# USB_HUB.net
KiCad netlist of a schematic drawn in Altium Designer
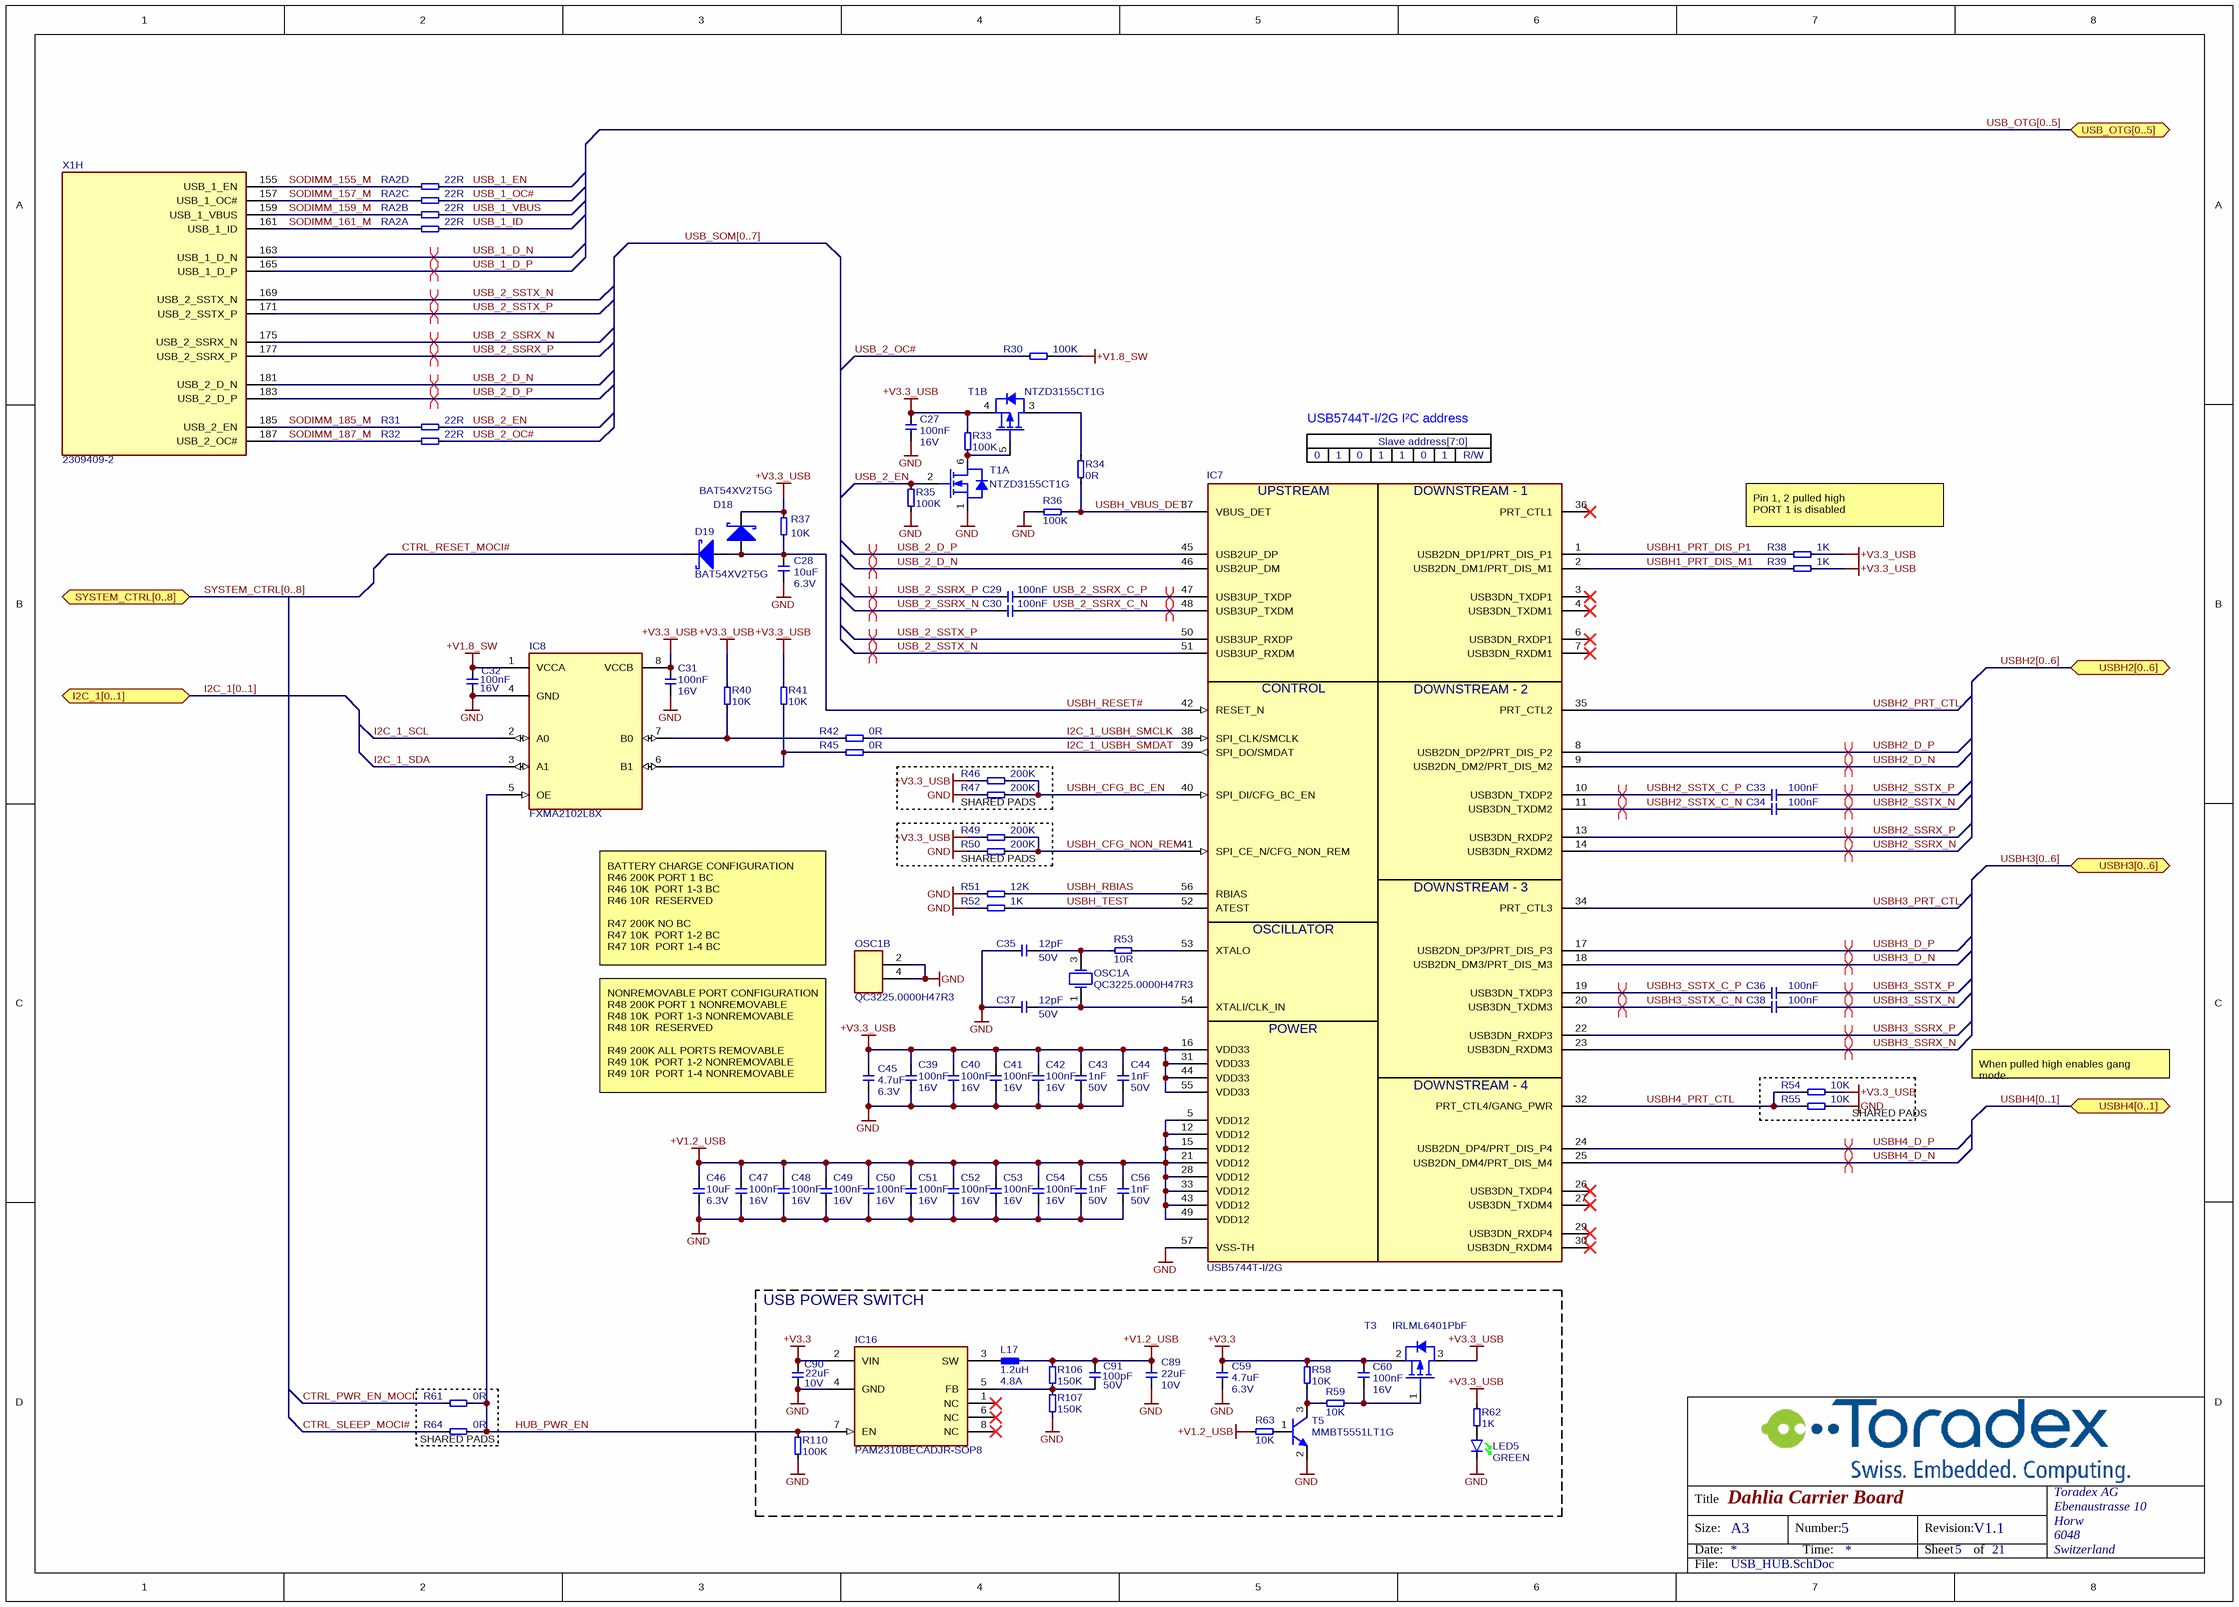
[diagram p0: USB_HUB.SchDoc]

(export (version "E")
  (design (tool "Eeschema 10.0.6"))
  (components
    (comp (ref "C27")
      (value "100nF")
      (footprint "CAPC1005X60N")
      (description "Capacitor Ceramic X7R 100nF 16V 10% 0402")
      (fields (field (name "TOLERANCE") "10%") (field (name "RATING") "16V"))
      (libsource (lib "Dahlia Carrier Board") (part "C-X7R-100nF-16V-10%-0402"))
    )
    (comp (ref "C28")
      (value "10uF")
      (footprint "CAPC1005X60N")
      (description "Capacitor Ceramic X5R 10uF 6.3V 20% 0402")
      (fields (field (name "TOLERANCE") "20%") (field (name "RATING") "6.3V"))
      (libsource (lib "Dahlia Carrier Board") (part "C-X5R-10u-6.3V-20%-0402"))
    )
    (comp (ref "C29")
      (value "100nF")
      (footprint "CAPC1005X60N")
      (description "Capacitor Ceramic X7R 100nF 16V 10% 0402")
      (fields (field (name "TOLERANCE") "10%"))
      (libsource (lib "Dahlia Carrier Board") (part "C-X7R-100nF-16V-10%-0402"))
    )
    (comp (ref "C30")
      (value "100nF")
      (footprint "CAPC1005X60N")
      (description "Capacitor Ceramic X7R 100nF 16V 10% 0402")
      (fields (field (name "TOLERANCE") "10%"))
      (libsource (lib "Dahlia Carrier Board") (part "C-X7R-100nF-16V-10%-0402"))
    )
    (comp (ref "C31")
      (value "100nF")
      (footprint "CAPC1005X60N")
      (description "Capacitor Ceramic X7R 100nF 16V 10% 0402")
      (fields (field (name "TOLERANCE") "10%") (field (name "RATING") "16V"))
      (libsource (lib "Dahlia Carrier Board") (part "C-X7R-100nF-16V-10%-0402"))
    )
    (comp (ref "C32")
      (value "100nF")
      (footprint "CAPC1005X60N")
      (description "Capacitor Ceramic X7R 100nF 16V 10% 0402")
      (fields (field (name "TOLERANCE") "10%") (field (name "RATING") "16V"))
      (libsource (lib "Dahlia Carrier Board") (part "C-X7R-100nF-16V-10%-0402"))
    )
    (comp (ref "C33")
      (value "100nF")
      (footprint "CAPC1005X60N")
      (description "Capacitor Ceramic X7R 100nF 16V 10% 0402")
      (fields (field (name "TOLERANCE") "10%"))
      (libsource (lib "Dahlia Carrier Board") (part "C-X7R-100nF-16V-10%-0402"))
    )
    (comp (ref "C34")
      (value "100nF")
      (footprint "CAPC1005X60N")
      (description "Capacitor Ceramic X7R 100nF 16V 10% 0402")
      (fields (field (name "TOLERANCE") "10%"))
      (libsource (lib "Dahlia Carrier Board") (part "C-X7R-100nF-16V-10%-0402"))
    )
    (comp (ref "C35")
      (value "12pF")
      (footprint "CAPC1005X60N")
      (description "Capacitor Ceramic NP0  12pF 50V 5% 0402")
      (fields (field (name "TOLERANCE") "5%") (field (name "RATING") "50V"))
      (libsource (lib "Dahlia Carrier Board") (part "C-NP0-12p-50V-5%-0402"))
    )
    (comp (ref "C36")
      (value "100nF")
      (footprint "CAPC1005X60N")
      (description "Capacitor Ceramic X7R 100nF 16V 10% 0402")
      (fields (field (name "TOLERANCE") "10%"))
      (libsource (lib "Dahlia Carrier Board") (part "C-X7R-100nF-16V-10%-0402"))
    )
    (comp (ref "C37")
      (value "12pF")
      (footprint "CAPC1005X60N")
      (description "Capacitor Ceramic NP0  12pF 50V 5% 0402")
      (fields (field (name "TOLERANCE") "5%") (field (name "RATING") "50V"))
      (libsource (lib "Dahlia Carrier Board") (part "C-NP0-12p-50V-5%-0402"))
    )
    (comp (ref "C38")
      (value "100nF")
      (footprint "CAPC1005X60N")
      (description "Capacitor Ceramic X7R 100nF 16V 10% 0402")
      (fields (field (name "TOLERANCE") "10%"))
      (libsource (lib "Dahlia Carrier Board") (part "C-X7R-100nF-16V-10%-0402"))
    )
    (comp (ref "C39")
      (value "100nF")
      (footprint "CAPC1005X60N")
      (description "Capacitor Ceramic X7R 100nF 16V 10% 0402")
      (fields (field (name "TOLERANCE") "10%") (field (name "RATING") "16V"))
      (libsource (lib "Dahlia Carrier Board") (part "C-X7R-100nF-16V-10%-0402"))
    )
    (comp (ref "C40")
      (value "100nF")
      (footprint "CAPC1005X60N")
      (description "Capacitor Ceramic X7R 100nF 16V 10% 0402")
      (fields (field (name "TOLERANCE") "10%") (field (name "RATING") "16V"))
      (libsource (lib "Dahlia Carrier Board") (part "C-X7R-100nF-16V-10%-0402"))
    )
    (comp (ref "C41")
      (value "100nF")
      (footprint "CAPC1005X60N")
      (description "Capacitor Ceramic X7R 100nF 16V 10% 0402")
      (fields (field (name "TOLERANCE") "10%") (field (name "RATING") "16V"))
      (libsource (lib "Dahlia Carrier Board") (part "C-X7R-100nF-16V-10%-0402"))
    )
    (comp (ref "C42")
      (value "100nF")
      (footprint "CAPC1005X60N")
      (description "Capacitor Ceramic X7R 100nF 16V 10% 0402")
      (fields (field (name "TOLERANCE") "10%") (field (name "RATING") "16V"))
      (libsource (lib "Dahlia Carrier Board") (part "C-X7R-100nF-16V-10%-0402"))
    )
    (comp (ref "C43")
      (value "1nF")
      (footprint "CAPC1005X60N")
      (description "Capacitor Ceramic X7R 1nF 50V 10% 0402")
      (fields (field (name "TOLERANCE") "10%") (field (name "RATING") "50V"))
      (libsource (lib "Dahlia Carrier Board") (part "C-X7R-1nF-50V-10%-0402"))
    )
    (comp (ref "C44")
      (value "1nF")
      (footprint "CAPC1005X60N")
      (description "Capacitor Ceramic X7R 1nF 50V 10% 0402")
      (fields (field (name "TOLERANCE") "10%") (field (name "RATING") "50V"))
      (libsource (lib "Dahlia Carrier Board") (part "C-X7R-1nF-50V-10%-0402"))
    )
    (comp (ref "C45")
      (value "4.7uF")
      (footprint "CAPC1005X60N")
      (description "Capacitor Ceramic X5R 4.7uF 6.3V 20% 0402")
      (fields (field (name "TOLERANCE") "20%") (field (name "RATING") "6.3V"))
      (libsource (lib "Dahlia Carrier Board") (part "C-X5R-4.7u-6.3V-20%-0402"))
    )
    (comp (ref "C46")
      (value "10uF")
      (footprint "CAPC1005X60N")
      (description "Capacitor Ceramic X5R 10uF 6.3V 20% 0402")
      (fields (field (name "TOLERANCE") "20%") (field (name "RATING") "6.3V"))
      (libsource (lib "Dahlia Carrier Board") (part "C-X5R-10u-6.3V-20%-0402"))
    )
    (comp (ref "C47")
      (value "100nF")
      (footprint "CAPC1005X60N")
      (description "Capacitor Ceramic X7R 100nF 16V 10% 0402")
      (fields (field (name "TOLERANCE") "10%") (field (name "RATING") "16V"))
      (libsource (lib "Dahlia Carrier Board") (part "C-X7R-100nF-16V-10%-0402"))
    )
    (comp (ref "C48")
      (value "100nF")
      (footprint "CAPC1005X60N")
      (description "Capacitor Ceramic X7R 100nF 16V 10% 0402")
      (fields (field (name "TOLERANCE") "10%") (field (name "RATING") "16V"))
      (libsource (lib "Dahlia Carrier Board") (part "C-X7R-100nF-16V-10%-0402"))
    )
    (comp (ref "C49")
      (value "100nF")
      (footprint "CAPC1005X60N")
      (description "Capacitor Ceramic X7R 100nF 16V 10% 0402")
      (fields (field (name "TOLERANCE") "10%") (field (name "RATING") "16V"))
      (libsource (lib "Dahlia Carrier Board") (part "C-X7R-100nF-16V-10%-0402"))
    )
    (comp (ref "C50")
      (value "100nF")
      (footprint "CAPC1005X60N")
      (description "Capacitor Ceramic X7R 100nF 16V 10% 0402")
      (fields (field (name "TOLERANCE") "10%") (field (name "RATING") "16V"))
      (libsource (lib "Dahlia Carrier Board") (part "C-X7R-100nF-16V-10%-0402"))
    )
    (comp (ref "C51")
      (value "100nF")
      (footprint "CAPC1005X60N")
      (description "Capacitor Ceramic X7R 100nF 16V 10% 0402")
      (fields (field (name "TOLERANCE") "10%") (field (name "RATING") "16V"))
      (libsource (lib "Dahlia Carrier Board") (part "C-X7R-100nF-16V-10%-0402"))
    )
    (comp (ref "C52")
      (value "100nF")
      (footprint "CAPC1005X60N")
      (description "Capacitor Ceramic X7R 100nF 16V 10% 0402")
      (fields (field (name "TOLERANCE") "10%") (field (name "RATING") "16V"))
      (libsource (lib "Dahlia Carrier Board") (part "C-X7R-100nF-16V-10%-0402"))
    )
    (comp (ref "C53")
      (value "100nF")
      (footprint "CAPC1005X60N")
      (description "Capacitor Ceramic X7R 100nF 16V 10% 0402")
      (fields (field (name "TOLERANCE") "10%") (field (name "RATING") "16V"))
      (libsource (lib "Dahlia Carrier Board") (part "C-X7R-100nF-16V-10%-0402"))
    )
    (comp (ref "C54")
      (value "100nF")
      (footprint "CAPC1005X60N")
      (description "Capacitor Ceramic X7R 100nF 16V 10% 0402")
      (fields (field (name "TOLERANCE") "10%") (field (name "RATING") "16V"))
      (libsource (lib "Dahlia Carrier Board") (part "C-X7R-100nF-16V-10%-0402"))
    )
    (comp (ref "C55")
      (value "1nF")
      (footprint "CAPC1005X60N")
      (description "Capacitor Ceramic X7R 1nF 50V 10% 0402")
      (fields (field (name "TOLERANCE") "10%") (field (name "RATING") "50V"))
      (libsource (lib "Dahlia Carrier Board") (part "C-X7R-1nF-50V-10%-0402"))
    )
    (comp (ref "C56")
      (value "1nF")
      (footprint "CAPC1005X60N")
      (description "Capacitor Ceramic X7R 1nF 50V 10% 0402")
      (fields (field (name "TOLERANCE") "10%") (field (name "RATING") "50V"))
      (libsource (lib "Dahlia Carrier Board") (part "C-X7R-1nF-50V-10%-0402"))
    )
    (comp (ref "C59")
      (value "4.7uF")
      (footprint "CAPC1005X60N")
      (description "Capacitor Ceramic X5R 4.7uF 6.3V 20% 0402")
      (fields (field (name "TOLERANCE") "20%") (field (name "RATING") "6.3V"))
      (libsource (lib "Dahlia Carrier Board") (part "C-X5R-4.7u-6.3V-20%-0402"))
    )
    (comp (ref "C60")
      (value "100nF")
      (footprint "CAPC1005X60N")
      (description "Capacitor Ceramic X7R 100nF 16V 10% 0402")
      (fields (field (name "TOLERANCE") "10%") (field (name "RATING") "16V"))
      (libsource (lib "Dahlia Carrier Board") (part "C-X7R-100nF-16V-10%-0402"))
    )
    (comp (ref "C89")
      (value "22uF")
      (footprint "T_CAPC0805X125N")
      (description "Capacitor Ceramic X5R 22uF 10V 20% 0805")
      (fields (field (name "TOLERANCE") "20%") (field (name "RATING") "10V"))
      (libsource (lib "Dahlia Carrier Board") (part "C-X5R-22uF-10V-20%-0805"))
    )
    (comp (ref "C90")
      (value "22uF")
      (footprint "T_CAPC0805X125N")
      (description "Capacitor Ceramic X5R 22uF 10V 20% 0805")
      (fields (field (name "TOLERANCE") "20%") (field (name "RATING") "10V"))
      (libsource (lib "Dahlia Carrier Board") (part "C-X5R-22uF-10V-20%-0805"))
    )
    (comp (ref "C91")
      (value "100pF")
      (footprint "CAPC1005X60N")
      (description "Capacitor Ceramic X7R 100pF 50V 10% 0402")
      (fields (field (name "TOLERANCE") "10%") (field (name "RATING") "50V"))
      (libsource (lib "Dahlia Carrier Board") (part "C-X7R-100pF-50V-10%-0402"))
    )
    (comp (ref "D18")
      (value "BAT54XV2T5G")
      (footprint "SOD-523")
      (description "Schottky Barrier Rectifier")
      (fields (field (name "MANUFACTURER PART NO.") "BAT54XV2T5G"))
      (libsource (lib "Dahlia Carrier Board") (part "D-BAT54-SOD523"))
    )
    (comp (ref "D19")
      (value "BAT54XV2T5G")
      (footprint "SOD-523")
      (description "Schottky Barrier Rectifier")
      (fields (field (name "MANUFACTURER PART NO.") "BAT54XV2T5G"))
      (libsource (lib "Dahlia Carrier Board") (part "D-BAT54-SOD523"))
    )
    (comp (ref "IC7")
      (value "USB5744T-I/2G")
      (footprint "IC-QFN40P700X700X100_HS-57N")
      (description "4-Port SS/HS USB 3.0 Controller Hub, VQFN-56, -40C to +85C")
      (libsource (lib "Dahlia Carrier Board") (part "IC-Microchip-USB5744T-I/2G"))
    )
    (comp (ref "IC8")
      (value "FXMA2102L8X")
      (footprint "IC-MicroPak50P160X2160X55-8N")
      (description "Voltage Level Translator for I2C Applications")
      (fields (field (name "MANUFACTURER PART NO.") "FXMA2102L8X"))
      (libsource (lib "Dahlia Carrier Board") (part "IC-ONsemi-FXMA2102L8X"))
    )
    (comp (ref "IC16")
      (value "PAM2310BECADJR")
      (footprint "IC-SO-8EP")
      (description "Integrated Buck Regulator")
      (fields (field (name "MANUFACTURER PART NO.") "PAM2310BECADJR-SOP8"))
      (libsource (lib "Dahlia Carrier Board") (part "IC-DIODES-PAM2310BECADJR-SOP8"))
    )
    (comp (ref "L17")
      (value "1.2uH")
      (footprint "IND-BOURNS-SRP4020TA")
      (description "1.2µH Shielded Wirewound Inductor 4.8A 30mOhm")
      (fields
        (field (name "TOLERANCE") "20%")
        (field (name "MANUFACTURER PART NO.") "SRP4020TA-1R2M")
        (field (name "RATING") "4.8A")
      )
      (libsource (lib "Dahlia Carrier Board") (part "L-Bourns-SRP4020TA-1R2M-1.2uH-4.8A-20%"))
    )
    (comp (ref "LED5")
      (value "LTST-C190GKT")
      (footprint "T_Liteon_LTST-C190GKT")
      (description "LED green Lite-ON LTST-C190GKT")
      (fields (field (name "COLOR") "GREEN"))
      (libsource (lib "Dahlia Carrier Board") (part "LED-LiteOn-LTST-C190GKT"))
    )
    (comp (ref "OSC1")
      (value "QC3225.0000H47R3")
      (footprint "OSC-SMD-3.2mmx2.5mm")
      (description "25MHz Crystal Oscillator, Qantek QC3225.0000H47R3, 20ppm, -40C to +85C, 10pF")
      (fields (field (name "TOLERANCE") "+/- 20 ppm"))
      (libsource (lib "Dahlia Carrier Board") (part "OSC-Qantek-QC3225.0000H47R3"))
    )
    (comp (ref "R30")
      (value "100K")
      (footprint "RESC1005X40N")
      (description "Resistor 100 Kohm 63mW 5% 0402")
      (fields (field (name "TOLERANCE") "5%"))
      (libsource (lib "Dahlia Carrier Board") (part "R-100K-63mW-5%-0402"))
    )
    (comp (ref "R31")
      (value "22R")
      (footprint "RESC1005X40N")
      (description "Resistor 22 ohm 63mW 5% 0402")
      (fields (field (name "TOLERANCE") "5%"))
      (libsource (lib "Dahlia Carrier Board") (part "R-22R-63mW-5%-0402"))
    )
    (comp (ref "R32")
      (value "22R")
      (footprint "RESC1005X40N")
      (description "Resistor 22 ohm 63mW 5% 0402")
      (fields (field (name "TOLERANCE") "5%"))
      (libsource (lib "Dahlia Carrier Board") (part "R-22R-63mW-5%-0402"))
    )
    (comp (ref "R33")
      (value "100K")
      (footprint "RESC1005X40N")
      (description "Resistor 100 Kohm 63mW 5% 0402")
      (fields (field (name "TOLERANCE") "5%"))
      (libsource (lib "Dahlia Carrier Board") (part "R-100K-63mW-5%-0402"))
    )
    (comp (ref "R34")
      (value "0R")
      (footprint "T_RESC0603X30N")
      (description "Resistor 0 ohm 63mW 1% 0603")
      (fields (field (name "TOLERANCE") "1%"))
      (libsource (lib "Dahlia Carrier Board") (part "R-0R-63mW-1%-0603"))
    )
    (comp (ref "R35")
      (value "100K")
      (footprint "RESC1005X40N")
      (description "Resistor 100 Kohm 63mW 5% 0402")
      (fields (field (name "TOLERANCE") "5%"))
      (libsource (lib "Dahlia Carrier Board") (part "R-100K-63mW-5%-0402"))
    )
    (comp (ref "R36")
      (value "100K")
      (footprint "RESC1005X40N")
      (description "Resistor 100 Kohm 63mW 5% 0402")
      (fields (field (name "TOLERANCE") "5%"))
      (libsource (lib "Dahlia Carrier Board") (part "R-100K-63mW-5%-0402"))
    )
    (comp (ref "R37")
      (value "10K")
      (footprint "RESC1005X40N")
      (description "Resistor 10 Kohm 63mW 5% 0402")
      (fields (field (name "TOLERANCE") "5%"))
      (libsource (lib "Dahlia Carrier Board") (part "R-10K-63mW-5%-0402"))
    )
    (comp (ref "R38")
      (value "1K")
      (footprint "RESC1005X40N")
      (description "Resistor 1 Kohm 63mW 5% 0402")
      (fields (field (name "TOLERANCE") "5%"))
      (libsource (lib "Dahlia Carrier Board") (part "R-1K-63mW-5%-0402"))
    )
    (comp (ref "R39")
      (value "1K")
      (footprint "RESC1005X40N")
      (description "Resistor 1 Kohm 63mW 5% 0402")
      (fields (field (name "TOLERANCE") "5%"))
      (libsource (lib "Dahlia Carrier Board") (part "R-1K-63mW-5%-0402"))
    )
    (comp (ref "R40")
      (value "10K")
      (footprint "RESC1005X40N")
      (description "Resistor 10 Kohm 63mW 5% 0402")
      (fields (field (name "TOLERANCE") "5%"))
      (libsource (lib "Dahlia Carrier Board") (part "R-10K-63mW-5%-0402"))
    )
    (comp (ref "R41")
      (value "10K")
      (footprint "RESC1005X40N")
      (description "Resistor 10 Kohm 63mW 5% 0402")
      (fields (field (name "TOLERANCE") "5%"))
      (libsource (lib "Dahlia Carrier Board") (part "R-10K-63mW-5%-0402"))
    )
    (comp (ref "R42")
      (value "0R")
      (footprint "T_RESC0603X30N")
      (description "Resistor 0 ohm 63mW 1% 0603")
      (fields (field (name "TOLERANCE") "1%"))
      (libsource (lib "Dahlia Carrier Board") (part "R-0R-63mW-1%-0603"))
    )
    (comp (ref "R45")
      (value "0R")
      (footprint "T_RESC0603X30N")
      (description "Resistor 0 ohm 63mW 1% 0603")
      (fields (field (name "TOLERANCE") "1%"))
      (libsource (lib "Dahlia Carrier Board") (part "R-0R-63mW-1%-0603"))
    )
    (comp (ref "R46")
      (value "200K")
      (footprint "T_RESC0603X30N")
      (description "Resistor 200 Kohm 63mW 5% 0603")
      (fields (field (name "TOLERANCE") "5%"))
      (libsource (lib "Dahlia Carrier Board") (part "R-200K-63mW-5%-0603"))
    )
    (comp (ref "R47")
      (value "200K")
      (footprint "T_RESC0603X30N")
      (description "Resistor 200 Kohm 63mW 5% 0603")
      (fields (field (name "TOLERANCE") "5%"))
      (libsource (lib "Dahlia Carrier Board") (part "R-200K-63mW-5%-0603"))
    )
    (comp (ref "R49")
      (value "200K")
      (footprint "T_RESC0603X30N")
      (description "Resistor 200 Kohm 63mW 5% 0603")
      (fields (field (name "TOLERANCE") "5%"))
      (libsource (lib "Dahlia Carrier Board") (part "R-200K-63mW-5%-0603"))
    )
    (comp (ref "R50")
      (value "200K")
      (footprint "T_RESC0603X30N")
      (description "Resistor 200 Kohm 63mW 5% 0603")
      (fields (field (name "TOLERANCE") "5%"))
      (libsource (lib "Dahlia Carrier Board") (part "R-200K-63mW-5%-0603"))
    )
    (comp (ref "R51")
      (value "12K")
      (footprint "RESC1005X40N")
      (description "Resistor 12 Kohm 63mW 1% 0402")
      (fields (field (name "TOLERANCE") "1%"))
      (libsource (lib "Dahlia Carrier Board") (part "R-12K-63mW-1%-0402"))
    )
    (comp (ref "R52")
      (value "1K")
      (footprint "RESC1005X40N")
      (description "Resistor 1 Kohm 63mW 5% 0402")
      (fields (field (name "TOLERANCE") "5%"))
      (libsource (lib "Dahlia Carrier Board") (part "R-1K-63mW-5%-0402"))
    )
    (comp (ref "R53")
      (value "10R")
      (footprint "RESC1005X40N")
      (description "Resistor 10 ohm 63mW 5% 0402")
      (fields (field (name "TOLERANCE") "5%"))
      (libsource (lib "Dahlia Carrier Board") (part "R-10R-63mW-5%-0402"))
    )
    (comp (ref "R54")
      (value "10K")
      (footprint "T_RESC0603X30N")
      (description "Resistor 10 Kohm 63mW 5% 0603")
      (fields (field (name "TOLERANCE") "5%"))
      (libsource (lib "Dahlia Carrier Board") (part "R-10K-63mW-5%-0603"))
    )
    (comp (ref "R55")
      (value "10K")
      (footprint "T_RESC0603X30N")
      (description "Resistor 10 Kohm 63mW 5% 0603")
      (fields (field (name "TOLERANCE") "5%"))
      (libsource (lib "Dahlia Carrier Board") (part "R-10K-63mW-5%-0603"))
    )
    (comp (ref "R58")
      (value "10K")
      (footprint "RESC1005X40N")
      (description "Resistor 10 Kohm 63mW 5% 0402")
      (fields (field (name "TOLERANCE") "5%"))
      (libsource (lib "Dahlia Carrier Board") (part "R-10K-63mW-5%-0402"))
    )
    (comp (ref "R59")
      (value "10K")
      (footprint "RESC1005X40N")
      (description "Resistor 10 Kohm 63mW 5% 0402")
      (fields (field (name "TOLERANCE") "5%"))
      (libsource (lib "Dahlia Carrier Board") (part "R-10K-63mW-5%-0402"))
    )
    (comp (ref "R61")
      (value "0R")
      (footprint "T_RESC0603X30N")
      (description "Resistor 0 ohm 63mW 1% 0603")
      (fields (field (name "TOLERANCE") "1%"))
      (libsource (lib "Dahlia Carrier Board") (part "R-0R-63mW-1%-0603"))
    )
    (comp (ref "R62")
      (value "1K")
      (footprint "RESC1005X40N")
      (description "Resistor 1 Kohm 63mW 5% 0402")
      (fields (field (name "TOLERANCE") "5%"))
      (libsource (lib "Dahlia Carrier Board") (part "R-1K-63mW-5%-0402"))
    )
    (comp (ref "R63")
      (value "10K")
      (footprint "RESC1005X40N")
      (description "Resistor 10 Kohm 63mW 5% 0402")
      (fields (field (name "TOLERANCE") "5%"))
      (libsource (lib "Dahlia Carrier Board") (part "R-10K-63mW-5%-0402"))
    )
    (comp (ref "R64")
      (value "0R")
      (footprint "T_RESC0603X30N")
      (description "Resistor 0 ohm 63mW 1% 0603")
      (fields (field (name "TOLERANCE") "1%"))
      (libsource (lib "Dahlia Carrier Board") (part "R-0R-63mW-1%-0603"))
    )
    (comp (ref "R106")
      (value "150K")
      (footprint "RESC1005X40N")
      (description "Resistor 150 Kohm 63mW 1% 0402")
      (fields (field (name "TOLERANCE") "1%"))
      (libsource (lib "Dahlia Carrier Board") (part "R-150K-63mW-1%-0402"))
    )
    (comp (ref "R107")
      (value "150K")
      (footprint "RESC1005X40N")
      (description "Resistor 150 Kohm 63mW 1% 0402")
      (fields (field (name "TOLERANCE") "1%"))
      (libsource (lib "Dahlia Carrier Board") (part "R-150K-63mW-1%-0402"))
    )
    (comp (ref "R110")
      (value "100K")
      (footprint "RESC1005X40N")
      (description "Resistor 100 Kohm 63mW 5% 0402")
      (fields (field (name "TOLERANCE") "5%"))
      (libsource (lib "Dahlia Carrier Board") (part "R-100K-63mW-5%-0402"))
    )
    (comp (ref "RA2")
      (value "22R")
      (footprint "T_Resistor_Array_X4")
      (description "Resistor Array 22 R 63mW 5% 1206")
      (fields (field (name "TOLERANCE") "5%"))
      (libsource (lib "Dahlia Carrier Board") (part "RA-22R-63mW-5%-1206-div"))
    )
    (comp (ref "T1")
      (value "NTZD3155CT1G")
      (footprint "SOTFL50P160X60-6N")
      (description "N- and P-Channel MOSFET 20V")
      (fields (field (name "MANUFACTURER PART NO.") "NTZD3155CT1G"))
      (libsource (lib "Dahlia Carrier Board") (part "T-ONSemi-NTZD3155CT1G"))
    )
    (comp (ref "T3")
      (value "IRLML6401PbF")
      (footprint "SOT95P237X112-3N")
      (description "p-channel MOSFET, IRLML6401PbF")
      (libsource (lib "Dahlia Carrier Board") (part "T-IR-IRLML6401PbF-SOT-23"))
    )
    (comp (ref "T5")
      (value "MMBT5551LT1G")
      (footprint "ONSC-SOT-23-3-318-08_V")
      (description "Bipolar Transistor NPN 160V 600mA  225mW Surface Mount SOT-23-3")
      (libsource (lib "Dahlia Carrier Board") (part "T-ONSemi-MMBT5551LT1G -SOT-23"))
    )
    (comp (ref "X1")
      (value "2309409-2")
      (footprint "CON-TE-2309409-2-SOLDERABLE-STANDOFFS")
      (description "DDR4 SODIMM Socket, 260 pins, 5.2mm(H), 0.5mm Pitch")
      (libsource (lib "Dahlia Carrier Board") (part "CON-TE-2309409-2"))
    )
  )
  (nets
    (net (code "42") (name "+V1.2_USB") (class "Default")
      (node (ref "C46") (pin "2") (pinfunction "2_2") (pintype "passive"))
      (node (ref "C47") (pin "2") (pinfunction "2_2") (pintype "passive"))
      (node (ref "C48") (pin "2") (pinfunction "2_2") (pintype "passive"))
      (node (ref "C49") (pin "2") (pinfunction "2_2") (pintype "passive"))
      (node (ref "C50") (pin "2") (pinfunction "2_2") (pintype "passive"))
      (node (ref "C51") (pin "2") (pinfunction "2_2") (pintype "passive"))
      (node (ref "C52") (pin "2") (pinfunction "2_2") (pintype "passive"))
      (node (ref "C53") (pin "2") (pinfunction "2_2") (pintype "passive"))
      (node (ref "C54") (pin "2") (pinfunction "2_2") (pintype "passive"))
      (node (ref "C55") (pin "2") (pinfunction "2_2") (pintype "passive"))
      (node (ref "C56") (pin "2") (pinfunction "2_2") (pintype "passive"))
      (node (ref "C89") (pin "2") (pinfunction "2_2") (pintype "passive"))
      (node (ref "C91") (pin "2") (pinfunction "2_2") (pintype "passive"))
      (node (ref "IC7") (pin "12") (pinfunction "VDD12_12") (pintype "power_in"))
      (node (ref "IC7") (pin "15") (pinfunction "VDD12_15") (pintype "power_in"))
      (node (ref "IC7") (pin "21") (pinfunction "VDD12_21") (pintype "power_in"))
      (node (ref "IC7") (pin "28") (pinfunction "VDD12_28") (pintype "power_in"))
      (node (ref "IC7") (pin "33") (pinfunction "VDD12_33") (pintype "power_in"))
      (node (ref "IC7") (pin "43") (pinfunction "VDD12_43") (pintype "power_in"))
      (node (ref "IC7") (pin "49") (pinfunction "VDD12_49") (pintype "power_in"))
      (node (ref "IC7") (pin "5") (pinfunction "VDD12_5") (pintype "power_in"))
      (node (ref "L17") (pin "2") (pinfunction "2_2") (pintype "passive"))
      (node (ref "R106") (pin "2") (pinfunction "2_2") (pintype "passive"))
      (node (ref "R63") (pin "2") (pinfunction "2_2") (pintype "passive"))
    )
    (net (code "43") (name "+V1.8_SW") (class "Default")
      (node (ref "C32") (pin "2") (pinfunction "2_2") (pintype "passive"))
      (node (ref "IC8") (pin "1") (pinfunction "VCCA_1") (pintype "power_in"))
      (node (ref "R30") (pin "2") (pinfunction "2_2") (pintype "passive"))
    )
    (net (code "44") (name "+V3.3") (class "Default")
      (node (ref "C59") (pin "2") (pinfunction "2_2") (pintype "passive"))
      (node (ref "C60") (pin "2") (pinfunction "2_2") (pintype "passive"))
      (node (ref "C90") (pin "2") (pinfunction "2_2") (pintype "passive"))
      (node (ref "IC16") (pin "2") (pinfunction "VIN_2") (pintype "power_in"))
      (node (ref "R58") (pin "2") (pinfunction "2_2") (pintype "passive"))
      (node (ref "T3") (pin "2") (pinfunction "S_2") (pintype "passive"))
    )
    (net (code "45") (name "+V3.3_USB") (class "Default")
      (node (ref "C27") (pin "2") (pinfunction "2_2") (pintype "passive"))
      (node (ref "C31") (pin "2") (pinfunction "2_2") (pintype "passive"))
      (node (ref "C39") (pin "2") (pinfunction "2_2") (pintype "passive"))
      (node (ref "C40") (pin "2") (pinfunction "2_2") (pintype "passive"))
      (node (ref "C41") (pin "2") (pinfunction "2_2") (pintype "passive"))
      (node (ref "C42") (pin "2") (pinfunction "2_2") (pintype "passive"))
      (node (ref "C43") (pin "2") (pinfunction "2_2") (pintype "passive"))
      (node (ref "C44") (pin "2") (pinfunction "2_2") (pintype "passive"))
      (node (ref "C45") (pin "2") (pinfunction "2_2") (pintype "passive"))
      (node (ref "D18") (pin "C") (pinfunction "C_C") (pintype "passive"))
      (node (ref "IC7") (pin "16") (pinfunction "VDD33_16") (pintype "power_in"))
      (node (ref "IC7") (pin "31") (pinfunction "VDD33_31") (pintype "power_in"))
      (node (ref "IC7") (pin "44") (pinfunction "VDD33_44") (pintype "power_in"))
      (node (ref "IC7") (pin "55") (pinfunction "VDD33_55") (pintype "power_in"))
      (node (ref "IC8") (pin "8") (pinfunction "VCCB_8") (pintype "power_in"))
      (node (ref "R33") (pin "2") (pinfunction "2_2") (pintype "passive"))
      (node (ref "R37") (pin "2") (pinfunction "2_2") (pintype "passive"))
      (node (ref "R38") (pin "2") (pinfunction "2_2") (pintype "passive"))
      (node (ref "R39") (pin "2") (pinfunction "2_2") (pintype "passive"))
      (node (ref "R40") (pin "2") (pinfunction "2_2") (pintype "passive"))
      (node (ref "R41") (pin "2") (pinfunction "2_2") (pintype "passive"))
      (node (ref "R46") (pin "1") (pinfunction "1_1") (pintype "passive"))
      (node (ref "R49") (pin "1") (pinfunction "1_1") (pintype "passive"))
      (node (ref "R54") (pin "2") (pinfunction "2_2") (pintype "passive"))
      (node (ref "R62") (pin "2") (pinfunction "2_2") (pintype "passive"))
      (node (ref "T1") (pin "4") (pinfunction "S_4") (pintype "passive"))
      (node (ref "T3") (pin "3") (pinfunction "D_3") (pintype "passive"))
    )
    (net (code "46") (name "/CTRL_PWR_EN_MOCI") (class "Default")
      (node (ref "R61") (pin "1") (pinfunction "1_1") (pintype "passive"))
    )
    (net (code "47") (name "/CTRL_RESET_MOCI#") (class "Default")
      (node (ref "D19") (pin "C") (pinfunction "C_C") (pintype "passive"))
    )
    (net (code "48") (name "/CTRL_SLEEP_MOCI#") (class "Default")
      (node (ref "R64") (pin "1") (pinfunction "1_1") (pintype "passive"))
    )
    (net (code "49") (name "/HUB_PWR_EN") (class "Default")
      (node (ref "IC16") (pin "7") (pinfunction "EN_7") (pintype "input"))
      (node (ref "IC8") (pin "5") (pinfunction "OE_5") (pintype "input"))
      (node (ref "R110") (pin "2") (pinfunction "2_2") (pintype "passive"))
      (node (ref "R61") (pin "2") (pinfunction "2_2") (pintype "passive"))
      (node (ref "R64") (pin "2") (pinfunction "2_2") (pintype "passive"))
    )
    (net (code "51") (name "/I2C_1_SCL") (class "Default")
      (node (ref "IC8") (pin "2") (pinfunction "A0_2") (pintype "bidirectional"))
    )
    (net (code "52") (name "/I2C_1_SDA") (class "Default")
      (node (ref "IC8") (pin "3") (pinfunction "A1_3") (pintype "bidirectional"))
    )
    (net (code "53") (name "/I2C_1_USBH_SMCLK") (class "Default")
      (node (ref "IC7") (pin "38") (pinfunction "SPI_CLK/SMCLK_38") (pintype "input"))
      (node (ref "R42") (pin "2") (pinfunction "2_2") (pintype "passive"))
    )
    (net (code "54") (name "/I2C_1_USBH_SMDAT") (class "Default")
      (node (ref "IC7") (pin "39") (pinfunction "SPI_DO/SMDAT_39") (pintype "output"))
      (node (ref "R45") (pin "2") (pinfunction "2_2") (pintype "passive"))
    )
    (net (code "55") (name "/SODIMM_155_M") (class "Default")
      (node (ref "RA2") (pin "4") (pinfunction "4_4") (pintype "passive"))
      (node (ref "X1") (pin "155") (pinfunction "USB_1_EN_155") (pintype "passive"))
    )
    (net (code "56") (name "/SODIMM_157_M") (class "Default")
      (node (ref "RA2") (pin "3") (pinfunction "3_3") (pintype "passive"))
      (node (ref "X1") (pin "157") (pinfunction "USB_1_OC#_157") (pintype "power_in"))
    )
    (net (code "57") (name "/SODIMM_159_M") (class "Default")
      (node (ref "RA2") (pin "2") (pinfunction "2_2") (pintype "passive"))
      (node (ref "X1") (pin "159") (pinfunction "USB_1_VBUS_159") (pintype "power_in"))
    )
    (net (code "58") (name "/SODIMM_161_M") (class "Default")
      (node (ref "RA2") (pin "1") (pinfunction "1_1") (pintype "passive"))
      (node (ref "X1") (pin "161") (pinfunction "USB_1_ID_161") (pintype "passive"))
    )
    (net (code "59") (name "/SODIMM_185_M") (class "Default")
      (node (ref "R31") (pin "1") (pinfunction "1_1") (pintype "passive"))
      (node (ref "X1") (pin "185") (pinfunction "USB_2_EN_185") (pintype "passive"))
    )
    (net (code "60") (name "/SODIMM_187_M") (class "Default")
      (node (ref "R32") (pin "1") (pinfunction "1_1") (pintype "passive"))
      (node (ref "X1") (pin "187") (pinfunction "USB_2_OC#_187") (pintype "passive"))
    )
    (net (code "62") (name "/USBH1_PRT_DIS_M1") (class "Default")
      (node (ref "IC7") (pin "2") (pinfunction "USB2DN_DM1/PRT_DIS_M1_2") (pintype "passive"))
      (node (ref "R39") (pin "1") (pinfunction "1_1") (pintype "passive"))
    )
    (net (code "63") (name "/USBH1_PRT_DIS_P1") (class "Default")
      (node (ref "IC7") (pin "1") (pinfunction "USB2DN_DP1/PRT_DIS_P1_1") (pintype "passive"))
      (node (ref "R38") (pin "1") (pinfunction "1_1") (pintype "passive"))
    )
    (net (code "65") (name "/USBH2_D_N") (class "Default")
      (node (ref "IC7") (pin "9") (pinfunction "USB2DN_DM2/PRT_DIS_M2_9") (pintype "passive"))
    )
    (net (code "66") (name "/USBH2_D_P") (class "Default")
      (node (ref "IC7") (pin "8") (pinfunction "USB2DN_DP2/PRT_DIS_P2_8") (pintype "passive"))
    )
    (net (code "67") (name "/USBH2_PRT_CTL") (class "Default")
      (node (ref "IC7") (pin "35") (pinfunction "PRT_CTL2_35") (pintype "passive"))
    )
    (net (code "68") (name "/USBH2_SSRX_N") (class "Default")
      (node (ref "IC7") (pin "14") (pinfunction "USB3DN_RXDM2_14") (pintype "passive"))
    )
    (net (code "69") (name "/USBH2_SSRX_P") (class "Default")
      (node (ref "IC7") (pin "13") (pinfunction "USB3DN_RXDP2_13") (pintype "passive"))
    )
    (net (code "70") (name "/USBH2_SSTX_C_N") (class "Default")
      (node (ref "C34") (pin "2") (pinfunction "2_2") (pintype "passive"))
      (node (ref "IC7") (pin "11") (pinfunction "USB3DN_TXDM2_11") (pintype "passive"))
    )
    (net (code "71") (name "/USBH2_SSTX_C_P") (class "Default")
      (node (ref "C33") (pin "2") (pinfunction "2_2") (pintype "passive"))
      (node (ref "IC7") (pin "10") (pinfunction "USB3DN_TXDP2_10") (pintype "passive"))
    )
    (net (code "72") (name "/USBH2_SSTX_N") (class "Default")
      (node (ref "C34") (pin "1") (pinfunction "1_1") (pintype "passive"))
    )
    (net (code "73") (name "/USBH2_SSTX_P") (class "Default")
      (node (ref "C33") (pin "1") (pinfunction "1_1") (pintype "passive"))
    )
    (net (code "75") (name "/USBH3_D_N") (class "Default")
      (node (ref "IC7") (pin "18") (pinfunction "USB2DN_DM3/PRT_DIS_M3_18") (pintype "passive"))
    )
    (net (code "76") (name "/USBH3_D_P") (class "Default")
      (node (ref "IC7") (pin "17") (pinfunction "USB2DN_DP3/PRT_DIS_P3_17") (pintype "passive"))
    )
    (net (code "77") (name "/USBH3_PRT_CTL") (class "Default")
      (node (ref "IC7") (pin "34") (pinfunction "PRT_CTL3_34") (pintype "passive"))
    )
    (net (code "78") (name "/USBH3_SSRX_N") (class "Default")
      (node (ref "IC7") (pin "23") (pinfunction "USB3DN_RXDM3_23") (pintype "passive"))
    )
    (net (code "79") (name "/USBH3_SSRX_P") (class "Default")
      (node (ref "IC7") (pin "22") (pinfunction "USB3DN_RXDP3_22") (pintype "passive"))
    )
    (net (code "80") (name "/USBH3_SSTX_C_N") (class "Default")
      (node (ref "C38") (pin "2") (pinfunction "2_2") (pintype "passive"))
      (node (ref "IC7") (pin "20") (pinfunction "USB3DN_TXDM3_20") (pintype "passive"))
    )
    (net (code "81") (name "/USBH3_SSTX_C_P") (class "Default")
      (node (ref "C36") (pin "2") (pinfunction "2_2") (pintype "passive"))
      (node (ref "IC7") (pin "19") (pinfunction "USB3DN_TXDP3_19") (pintype "passive"))
    )
    (net (code "82") (name "/USBH3_SSTX_N") (class "Default")
      (node (ref "C38") (pin "1") (pinfunction "1_1") (pintype "passive"))
    )
    (net (code "83") (name "/USBH3_SSTX_P") (class "Default")
      (node (ref "C36") (pin "1") (pinfunction "1_1") (pintype "passive"))
    )
    (net (code "85") (name "/USBH4_D_N") (class "Default")
      (node (ref "IC7") (pin "25") (pinfunction "USB2DN_DM4/PRT_DIS_M4_25") (pintype "passive"))
    )
    (net (code "86") (name "/USBH4_D_P") (class "Default")
      (node (ref "IC7") (pin "24") (pinfunction "USB2DN_DP4/PRT_DIS_P4_24") (pintype "passive"))
    )
    (net (code "87") (name "/USBH4_PRT_CTL") (class "Default")
      (node (ref "IC7") (pin "32") (pinfunction "PRT_CTL4/GANG_PWR_32") (pintype "passive"))
      (node (ref "R54") (pin "1") (pinfunction "1_1") (pintype "passive"))
      (node (ref "R55") (pin "1") (pinfunction "1_1") (pintype "passive"))
    )
    (net (code "88") (name "/USBH_CFG_BC_EN") (class "Default")
      (node (ref "IC7") (pin "40") (pinfunction "SPI_DI/CFG_BC_EN_40") (pintype "input"))
      (node (ref "R46") (pin "2") (pinfunction "2_2") (pintype "passive"))
      (node (ref "R47") (pin "2") (pinfunction "2_2") (pintype "passive"))
    )
    (net (code "89") (name "/USBH_CFG_NON_REM") (class "Default")
      (node (ref "IC7") (pin "41") (pinfunction "SPI_CE_N/CFG_NON_REM_41") (pintype "input"))
      (node (ref "R49") (pin "2") (pinfunction "2_2") (pintype "passive"))
      (node (ref "R50") (pin "2") (pinfunction "2_2") (pintype "passive"))
    )
    (net (code "90") (name "/USBH_RBIAS") (class "Default")
      (node (ref "IC7") (pin "56") (pinfunction "RBIAS_56") (pintype "passive"))
      (node (ref "R51") (pin "2") (pinfunction "2_2") (pintype "passive"))
    )
    (net (code "91") (name "/USBH_RESET#") (class "Default")
      (node (ref "C28") (pin "2") (pinfunction "2_2") (pintype "passive"))
      (node (ref "D18") (pin "A") (pinfunction "A_A") (pintype "passive"))
      (node (ref "D19") (pin "A") (pinfunction "A_A") (pintype "passive"))
      (node (ref "IC7") (pin "42") (pinfunction "RESET_N_42") (pintype "input"))
      (node (ref "R37") (pin "1") (pinfunction "1_1") (pintype "passive"))
    )
    (net (code "92") (name "/USBH_TEST") (class "Default")
      (node (ref "IC7") (pin "52") (pinfunction "ATEST_52") (pintype "passive"))
      (node (ref "R52") (pin "2") (pinfunction "2_2") (pintype "passive"))
    )
    (net (code "93") (name "/USBH_VBUS_DET") (class "Default")
      (node (ref "IC7") (pin "37") (pinfunction "VBUS_DET_37") (pintype "passive"))
      (node (ref "R34") (pin "2") (pinfunction "2_2") (pintype "passive"))
      (node (ref "R36") (pin "1") (pinfunction "1_1") (pintype "passive"))
    )
    (net (code "94") (name "/USB_1_D_N") (class "Default")
      (node (ref "X1") (pin "163") (pinfunction "USB_1_D_N_163") (pintype "power_in"))
    )
    (net (code "95") (name "/USB_1_D_P") (class "Default")
      (node (ref "X1") (pin "165") (pinfunction "USB_1_D_P_165") (pintype "passive"))
    )
    (net (code "96") (name "/USB_1_EN") (class "Default")
      (node (ref "RA2") (pin "8") (pinfunction "8_8") (pintype "passive"))
    )
    (net (code "97") (name "/USB_1_ID") (class "Default")
      (node (ref "RA2") (pin "5") (pinfunction "5_5") (pintype "passive"))
    )
    (net (code "98") (name "/USB_1_OC#") (class "Default")
      (node (ref "RA2") (pin "7") (pinfunction "7_7") (pintype "passive"))
    )
    (net (code "99") (name "/USB_1_VBUS") (class "Default")
      (node (ref "RA2") (pin "6") (pinfunction "6_6") (pintype "passive"))
    )
    (net (code "100") (name "/USB_2_D_N") (class "Default")
      (node (ref "IC7") (pin "46") (pinfunction "USB2UP_DM_46") (pintype "passive"))
      (node (ref "X1") (pin "181") (pinfunction "USB_2_D_N_181") (pintype "passive"))
    )
    (net (code "101") (name "/USB_2_D_P") (class "Default")
      (node (ref "IC7") (pin "45") (pinfunction "USB2UP_DP_45") (pintype "passive"))
      (node (ref "X1") (pin "183") (pinfunction "USB_2_D_P_183") (pintype "passive"))
    )
    (net (code "102") (name "/USB_2_EN") (class "Default")
      (node (ref "R31") (pin "2") (pinfunction "2_2") (pintype "passive"))
      (node (ref "R35") (pin "2") (pinfunction "2_2") (pintype "passive"))
      (node (ref "T1") (pin "2") (pinfunction "G_2") (pintype "passive"))
    )
    (net (code "103") (name "/USB_2_OC#") (class "Default")
      (node (ref "R30") (pin "1") (pinfunction "1_1") (pintype "passive"))
      (node (ref "R32") (pin "2") (pinfunction "2_2") (pintype "passive"))
    )
    (net (code "104") (name "/USB_2_SSRX_C_N") (class "Default")
      (node (ref "C30") (pin "1") (pinfunction "1_1") (pintype "passive"))
      (node (ref "IC7") (pin "48") (pinfunction "USB3UP_TXDM_48") (pintype "passive"))
    )
    (net (code "105") (name "/USB_2_SSRX_C_P") (class "Default")
      (node (ref "C29") (pin "1") (pinfunction "1_1") (pintype "passive"))
      (node (ref "IC7") (pin "47") (pinfunction "USB3UP_TXDP_47") (pintype "passive"))
    )
    (net (code "106") (name "/USB_2_SSRX_N") (class "Default")
      (node (ref "C30") (pin "2") (pinfunction "2_2") (pintype "passive"))
      (node (ref "X1") (pin "175") (pinfunction "USB_2_SSRX_N_175") (pintype "passive"))
    )
    (net (code "107") (name "/USB_2_SSRX_P") (class "Default")
      (node (ref "C29") (pin "2") (pinfunction "2_2") (pintype "passive"))
      (node (ref "X1") (pin "177") (pinfunction "USB_2_SSRX_P_177") (pintype "passive"))
    )
    (net (code "108") (name "/USB_2_SSTX_N") (class "Default")
      (node (ref "IC7") (pin "51") (pinfunction "USB3UP_RXDM_51") (pintype "passive"))
      (node (ref "X1") (pin "169") (pinfunction "USB_2_SSTX_N_169") (pintype "passive"))
    )
    (net (code "109") (name "/USB_2_SSTX_P") (class "Default")
      (node (ref "IC7") (pin "50") (pinfunction "USB3UP_RXDP_50") (pintype "passive"))
      (node (ref "X1") (pin "171") (pinfunction "USB_2_SSTX_P_171") (pintype "passive"))
    )
    (net (code "112") (name "GND") (class "Default")
      (node (ref "C27") (pin "1") (pinfunction "1_1") (pintype "passive"))
      (node (ref "C28") (pin "1") (pinfunction "1_1") (pintype "passive"))
      (node (ref "C31") (pin "1") (pinfunction "1_1") (pintype "passive"))
      (node (ref "C32") (pin "1") (pinfunction "1_1") (pintype "passive"))
      (node (ref "C35") (pin "2") (pinfunction "2_2") (pintype "passive"))
      (node (ref "C37") (pin "2") (pinfunction "2_2") (pintype "passive"))
      (node (ref "C39") (pin "1") (pinfunction "1_1") (pintype "passive"))
      (node (ref "C40") (pin "1") (pinfunction "1_1") (pintype "passive"))
      (node (ref "C41") (pin "1") (pinfunction "1_1") (pintype "passive"))
      (node (ref "C42") (pin "1") (pinfunction "1_1") (pintype "passive"))
      (node (ref "C43") (pin "1") (pinfunction "1_1") (pintype "passive"))
      (node (ref "C44") (pin "1") (pinfunction "1_1") (pintype "passive"))
      (node (ref "C45") (pin "1") (pinfunction "1_1") (pintype "passive"))
      (node (ref "C46") (pin "1") (pinfunction "1_1") (pintype "passive"))
      (node (ref "C47") (pin "1") (pinfunction "1_1") (pintype "passive"))
      (node (ref "C48") (pin "1") (pinfunction "1_1") (pintype "passive"))
      (node (ref "C49") (pin "1") (pinfunction "1_1") (pintype "passive"))
      (node (ref "C50") (pin "1") (pinfunction "1_1") (pintype "passive"))
      (node (ref "C51") (pin "1") (pinfunction "1_1") (pintype "passive"))
      (node (ref "C52") (pin "1") (pinfunction "1_1") (pintype "passive"))
      (node (ref "C53") (pin "1") (pinfunction "1_1") (pintype "passive"))
      (node (ref "C54") (pin "1") (pinfunction "1_1") (pintype "passive"))
      (node (ref "C55") (pin "1") (pinfunction "1_1") (pintype "passive"))
      (node (ref "C56") (pin "1") (pinfunction "1_1") (pintype "passive"))
      (node (ref "C59") (pin "1") (pinfunction "1_1") (pintype "passive"))
      (node (ref "C89") (pin "1") (pinfunction "1_1") (pintype "passive"))
      (node (ref "C90") (pin "1") (pinfunction "1_1") (pintype "passive"))
      (node (ref "IC16") (pin "4") (pinfunction "GND_4") (pintype "power_in"))
      (node (ref "IC7") (pin "57") (pinfunction "VSS-TH_57") (pintype "power_in"))
      (node (ref "IC8") (pin "4") (pinfunction "GND_4") (pintype "power_in"))
      (node (ref "LED5") (pin "K") (pinfunction "K_K") (pintype "passive"))
      (node (ref "OSC1") (pin "2") (pinfunction "OSC2_2") (pintype "passive"))
      (node (ref "OSC1") (pin "4") (pinfunction "OSC3_4") (pintype "passive"))
      (node (ref "R107") (pin "1") (pinfunction "1_1") (pintype "passive"))
      (node (ref "R110") (pin "1") (pinfunction "1_1") (pintype "passive"))
      (node (ref "R35") (pin "1") (pinfunction "1_1") (pintype "passive"))
      (node (ref "R36") (pin "2") (pinfunction "2_2") (pintype "passive"))
      (node (ref "R47") (pin "1") (pinfunction "1_1") (pintype "passive"))
      (node (ref "R50") (pin "1") (pinfunction "1_1") (pintype "passive"))
      (node (ref "R51") (pin "1") (pinfunction "1_1") (pintype "passive"))
      (node (ref "R52") (pin "1") (pinfunction "1_1") (pintype "passive"))
      (node (ref "R55") (pin "2") (pinfunction "2_2") (pintype "passive"))
      (node (ref "T1") (pin "1") (pinfunction "S_1") (pintype "passive"))
      (node (ref "T5") (pin "2") (pinfunction "E_2") (pintype "passive"))
    )
    (net (code "113") (name "Net-(IC7-XTALI{slash}CLK_IN)") (class "Default")
      (node (ref "C37") (pin "1") (pinfunction "1_1") (pintype "passive"))
      (node (ref "IC7") (pin "54") (pinfunction "XTALI/CLK_IN_54") (pintype "passive"))
      (node (ref "OSC1") (pin "1") (pinfunction "OSC1_1") (pintype "passive"))
    )
    (net (code "114") (name "Net-(IC7-XTALO)") (class "Default")
      (node (ref "IC7") (pin "53") (pinfunction "XTALO_53") (pintype "passive"))
      (node (ref "R53") (pin "2") (pinfunction "2_2") (pintype "passive"))
    )
    (net (code "115") (name "Net-(IC8-B0)") (class "Default")
      (node (ref "IC8") (pin "7") (pinfunction "B0_7") (pintype "bidirectional"))
      (node (ref "R40") (pin "1") (pinfunction "1_1") (pintype "passive"))
      (node (ref "R42") (pin "1") (pinfunction "1_1") (pintype "passive"))
    )
    (net (code "116") (name "Net-(IC8-B1)") (class "Default")
      (node (ref "IC8") (pin "6") (pinfunction "B1_6") (pintype "bidirectional"))
      (node (ref "R41") (pin "1") (pinfunction "1_1") (pintype "passive"))
      (node (ref "R45") (pin "1") (pinfunction "1_1") (pintype "passive"))
    )
    (net (code "117") (name "Net-(IC16-FB)") (class "Default")
      (node (ref "C91") (pin "1") (pinfunction "1_1") (pintype "passive"))
      (node (ref "IC16") (pin "5") (pinfunction "FB_5") (pintype "power_in"))
      (node (ref "R106") (pin "1") (pinfunction "1_1") (pintype "passive"))
      (node (ref "R107") (pin "2") (pinfunction "2_2") (pintype "passive"))
    )
    (net (code "118") (name "Net-(IC16-SW)") (class "Default")
      (node (ref "IC16") (pin "3") (pinfunction "SW_3") (pintype "power_in"))
      (node (ref "L17") (pin "1") (pinfunction "1_1") (pintype "passive"))
    )
    (net (code "119") (name "Net-(LED5-PadA)") (class "Default")
      (node (ref "LED5") (pin "A") (pinfunction "A_A") (pintype "passive"))
      (node (ref "R62") (pin "1") (pinfunction "1_1") (pintype "passive"))
    )
    (net (code "120") (name "Net-(OSC1A-OSC2)") (class "Default")
      (node (ref "C35") (pin "1") (pinfunction "1_1") (pintype "passive"))
      (node (ref "OSC1") (pin "3") (pinfunction "OSC2_3") (pintype "passive"))
      (node (ref "R53") (pin "1") (pinfunction "1_1") (pintype "passive"))
    )
    (net (code "121") (name "Net-(T1A-D)") (class "Default")
      (node (ref "R33") (pin "1") (pinfunction "1_1") (pintype "passive"))
      (node (ref "T1") (pin "5") (pinfunction "G_5") (pintype "passive"))
      (node (ref "T1") (pin "6") (pinfunction "D_6") (pintype "passive"))
    )
    (net (code "122") (name "Net-(T1B-D)") (class "Default")
      (node (ref "R34") (pin "1") (pinfunction "1_1") (pintype "passive"))
      (node (ref "T1") (pin "3") (pinfunction "D_3") (pintype "passive"))
    )
    (net (code "123") (name "Net-(T3-G)") (class "Default")
      (node (ref "C60") (pin "1") (pinfunction "1_1") (pintype "passive"))
      (node (ref "R59") (pin "1") (pinfunction "1_1") (pintype "passive"))
      (node (ref "T3") (pin "1") (pinfunction "G_1") (pintype "passive"))
    )
    (net (code "124") (name "Net-(T5-B)") (class "Default")
      (node (ref "R63") (pin "1") (pinfunction "1_1") (pintype "passive"))
      (node (ref "T5") (pin "1") (pinfunction "B_1") (pintype "passive"))
    )
    (net (code "125") (name "Net-(T5-C)") (class "Default")
      (node (ref "R58") (pin "1") (pinfunction "1_1") (pintype "passive"))
      (node (ref "R59") (pin "2") (pinfunction "2_2") (pintype "passive"))
      (node (ref "T5") (pin "3") (pinfunction "C_3") (pintype "passive"))
    )
    (net (code "126") (name "unconnected-(IC7-PRT_CTL1-Pad36)") (class "Default")
      (node (ref "IC7") (pin "36") (pinfunction "PRT_CTL1_36") (pintype "passive+no_connect"))
    )
    (net (code "127") (name "unconnected-(IC7-USB3DN_RXDM1-Pad7)") (class "Default")
      (node (ref "IC7") (pin "7") (pinfunction "USB3DN_RXDM1_7") (pintype "passive+no_connect"))
    )
    (net (code "128") (name "unconnected-(IC7-USB3DN_RXDM4-Pad30)") (class "Default")
      (node (ref "IC7") (pin "30") (pinfunction "USB3DN_RXDM4_30") (pintype "passive+no_connect"))
    )
    (net (code "129") (name "unconnected-(IC7-USB3DN_RXDP1-Pad6)") (class "Default")
      (node (ref "IC7") (pin "6") (pinfunction "USB3DN_RXDP1_6") (pintype "passive+no_connect"))
    )
    (net (code "130") (name "unconnected-(IC7-USB3DN_RXDP4-Pad29)") (class "Default")
      (node (ref "IC7") (pin "29") (pinfunction "USB3DN_RXDP4_29") (pintype "passive+no_connect"))
    )
    (net (code "131") (name "unconnected-(IC7-USB3DN_TXDM1-Pad4)") (class "Default")
      (node (ref "IC7") (pin "4") (pinfunction "USB3DN_TXDM1_4") (pintype "passive+no_connect"))
    )
    (net (code "132") (name "unconnected-(IC7-USB3DN_TXDM4-Pad27)") (class "Default")
      (node (ref "IC7") (pin "27") (pinfunction "USB3DN_TXDM4_27") (pintype "passive+no_connect"))
    )
    (net (code "133") (name "unconnected-(IC7-USB3DN_TXDP1-Pad3)") (class "Default")
      (node (ref "IC7") (pin "3") (pinfunction "USB3DN_TXDP1_3") (pintype "passive+no_connect"))
    )
    (net (code "134") (name "unconnected-(IC7-USB3DN_TXDP4-Pad26)") (class "Default")
      (node (ref "IC7") (pin "26") (pinfunction "USB3DN_TXDP4_26") (pintype "passive+no_connect"))
    )
    (net (code "135") (name "unconnected-(IC16-NC-Pad1)") (class "Default")
      (node (ref "IC16") (pin "1") (pinfunction "NC_1") (pintype "power_in+no_connect"))
    )
    (net (code "136") (name "unconnected-(IC16-NC-Pad6)") (class "Default")
      (node (ref "IC16") (pin "6") (pinfunction "NC_6") (pintype "power_in+no_connect"))
    )
    (net (code "137") (name "unconnected-(IC16-NC-Pad8)") (class "Default")
      (node (ref "IC16") (pin "8") (pinfunction "NC_8") (pintype "power_in+no_connect"))
    )
  )
)
